# EM7SEGClk.net
KiCad netlist of a schematic drawn in EAGLE
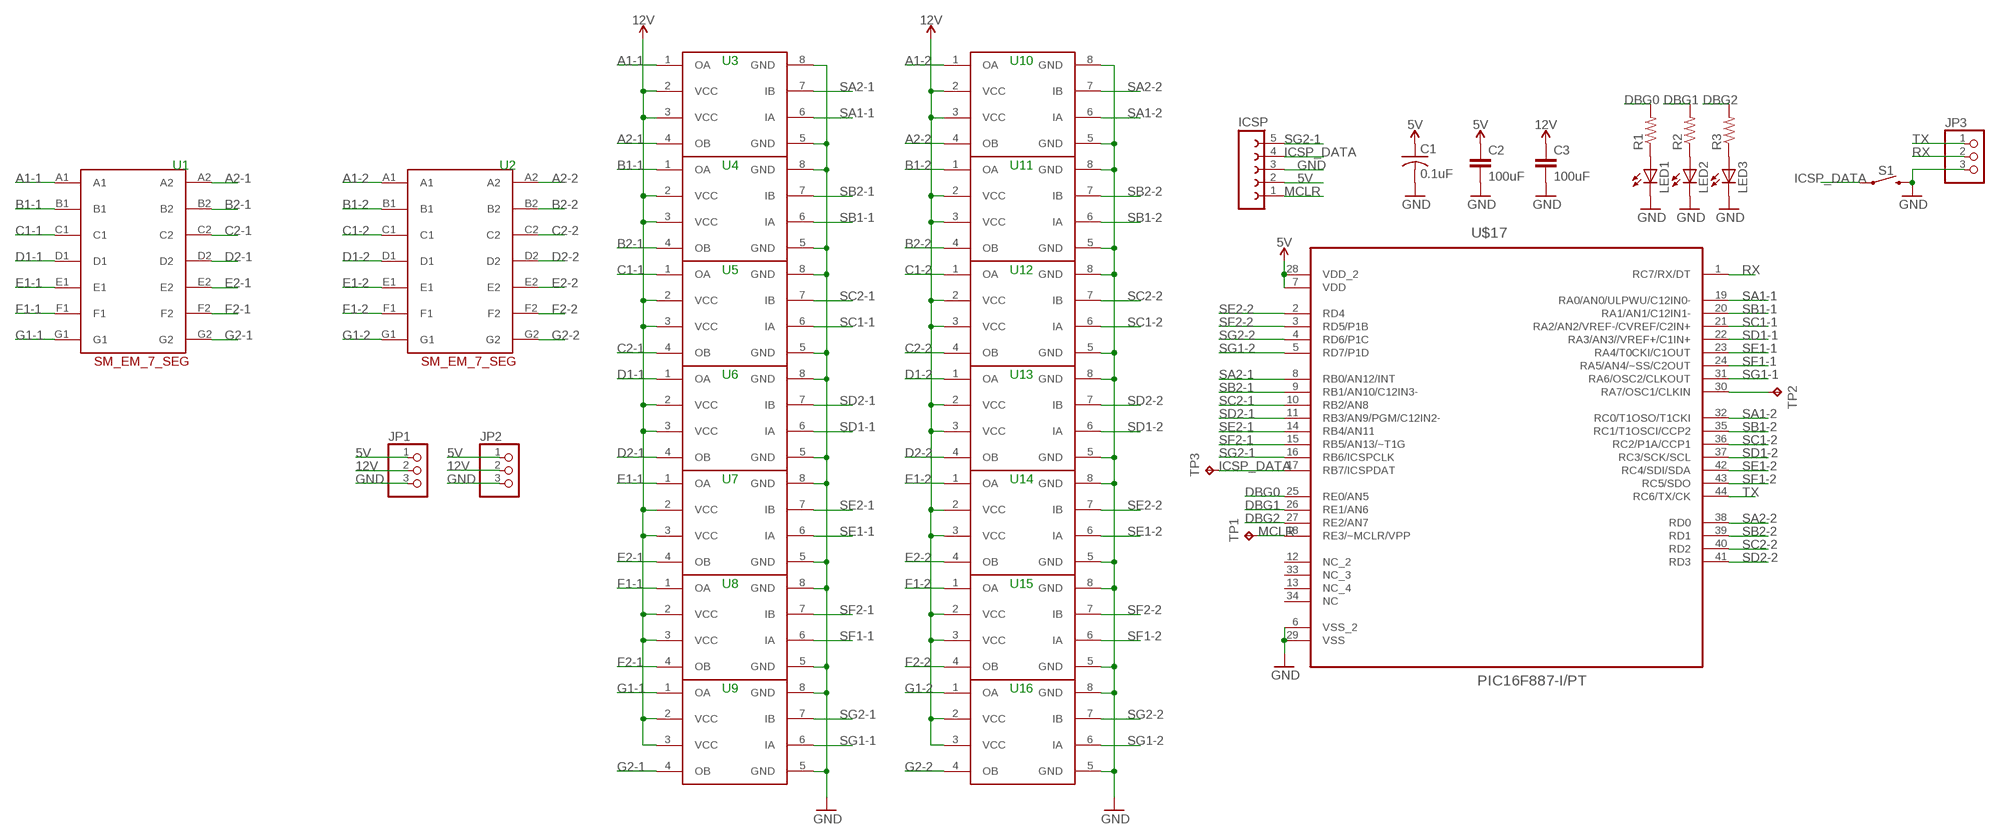
[diagram p0: schematic, sheet 1]

(export (version "E")
  (design (tool "Eeschema 10.0.6"))
  (components
    (comp (ref "C1")
      (value "0.1uF")
      (footprint "eagle-import:C0805")
      (libsource (lib "eagle-import") (part "C-USC0805"))
    )
    (comp (ref "C2")
      (value "100uF")
      (footprint "eagle-import:C5B2.5")
      (libsource (lib "eagle-import") (part "C5/2.5"))
    )
    (comp (ref "C3")
      (value "100uF")
      (footprint "eagle-import:C5B2.5")
      (libsource (lib "eagle-import") (part "C5/2.5"))
    )
    (comp (ref "ICSP")
      (value "FE05-1")
      (footprint "eagle-import:FE05-1")
      (libsource (lib "eagle-import") (part "FE05-1"))
    )
    (comp (ref "JP1")
      (value "PINHD-1X3CB")
      (footprint "eagle-import:1X03-CLEANBIG")
      (libsource (lib "eagle-import") (part "PINHD-1X3CB"))
    )
    (comp (ref "JP2")
      (value "PINHD-1X3CB")
      (footprint "eagle-import:1X03-CLEANBIG")
      (libsource (lib "eagle-import") (part "PINHD-1X3CB"))
    )
    (comp (ref "JP3")
      (value "PINHD-1X3CB")
      (footprint "eagle-import:1X03-CLEANBIG")
      (libsource (lib "eagle-import") (part "PINHD-1X3CB"))
    )
    (comp (ref "LED1")
      (value "LEDCHIPLED_0805")
      (footprint "eagle-import:CHIPLED_0805")
      (libsource (lib "eagle-import") (part "LEDCHIPLED_0805"))
    )
    (comp (ref "LED2")
      (value "LEDCHIPLED_0805")
      (footprint "eagle-import:CHIPLED_0805")
      (libsource (lib "eagle-import") (part "LEDCHIPLED_0805"))
    )
    (comp (ref "LED3")
      (value "LEDCHIPLED_0805")
      (footprint "eagle-import:CHIPLED_0805")
      (libsource (lib "eagle-import") (part "LEDCHIPLED_0805"))
    )
    (comp (ref "R1")
      (value "R-US_M0805")
      (footprint "eagle-import:M0805")
      (libsource (lib "eagle-import") (part "R-US_M0805"))
    )
    (comp (ref "R2")
      (value "R-US_M0805")
      (footprint "eagle-import:M0805")
      (libsource (lib "eagle-import") (part "R-US_M0805"))
    )
    (comp (ref "R3")
      (value "R-US_M0805")
      (footprint "eagle-import:M0805")
      (libsource (lib "eagle-import") (part "R-US_M0805"))
    )
    (comp (ref "S1")
      (value "MOMENTARY-SWITCH-SPST-PTH-6.0MM")
      (footprint "eagle-import:TACTILE_SWITCH_PTH_6.0MM")
      (libsource (lib "eagle-import") (part "MOMENTARY-SWITCH-SPST-PTH-6.0MM"))
    )
    (comp (ref "TP1")
      (value "TPTP16R")
      (footprint "eagle-import:TP16R")
      (libsource (lib "eagle-import") (part "TPTP16R"))
    )
    (comp (ref "TP2")
      (value "TPTP16R")
      (footprint "eagle-import:TP16R")
      (libsource (lib "eagle-import") (part "TPTP16R"))
    )
    (comp (ref "TP3")
      (value "TPTP16R")
      (footprint "eagle-import:TP16R")
      (libsource (lib "eagle-import") (part "TPTP16R"))
    )
    (comp (ref "U$1")
      (value "ELECTROMECHANICAL_7_SEG")
      (footprint "eagle-import:EM_7_SEG")
      (libsource (lib "eagle-import") (part "ELECTROMECHANICAL_7_SEG"))
    )
    (comp (ref "U$2")
      (value "ELECTROMECHANICAL_7_SEG")
      (footprint "eagle-import:EM_7_SEG")
      (libsource (lib "eagle-import") (part "ELECTROMECHANICAL_7_SEG"))
    )
    (comp (ref "U$3")
      (value "L9110SOP8")
      (footprint "eagle-import:SO8")
      (libsource (lib "eagle-import") (part "L9110SOP8"))
    )
    (comp (ref "U$4")
      (value "L9110SOP8")
      (footprint "eagle-import:SO8")
      (libsource (lib "eagle-import") (part "L9110SOP8"))
    )
    (comp (ref "U$5")
      (value "L9110SOP8")
      (footprint "eagle-import:SO8")
      (libsource (lib "eagle-import") (part "L9110SOP8"))
    )
    (comp (ref "U$6")
      (value "L9110SOP8")
      (footprint "eagle-import:SO8")
      (libsource (lib "eagle-import") (part "L9110SOP8"))
    )
    (comp (ref "U$7")
      (value "L9110SOP8")
      (footprint "eagle-import:SO8")
      (libsource (lib "eagle-import") (part "L9110SOP8"))
    )
    (comp (ref "U$8")
      (value "L9110SOP8")
      (footprint "eagle-import:SO8")
      (libsource (lib "eagle-import") (part "L9110SOP8"))
    )
    (comp (ref "U$9")
      (value "L9110SOP8")
      (footprint "eagle-import:SO8")
      (libsource (lib "eagle-import") (part "L9110SOP8"))
    )
    (comp (ref "U$10")
      (value "L9110SOP8")
      (footprint "eagle-import:SO8")
      (libsource (lib "eagle-import") (part "L9110SOP8"))
    )
    (comp (ref "U$14")
      (value "L9110SOP8")
      (footprint "eagle-import:SO8")
      (libsource (lib "eagle-import") (part "L9110SOP8"))
    )
    (comp (ref "U$15")
      (value "L9110SOP8")
      (footprint "eagle-import:SO8")
      (libsource (lib "eagle-import") (part "L9110SOP8"))
    )
    (comp (ref "U$16")
      (value "L9110SOP8")
      (footprint "eagle-import:SO8")
      (libsource (lib "eagle-import") (part "L9110SOP8"))
    )
    (comp (ref "U$17")
      (value "PIC16F887-I/PT")
      (footprint "eagle-import:QFP80P1200X1200X120-44N")
      (libsource (lib "eagle-import") (part "PIC16F887-I/PT"))
    )
    (comp (ref "U$140")
      (value "L9110SOP8")
      (footprint "eagle-import:SO8")
      (libsource (lib "eagle-import") (part "L9110SOP8"))
    )
    (comp (ref "U$150")
      (value "L9110SOP8")
      (footprint "eagle-import:SO8")
      (libsource (lib "eagle-import") (part "L9110SOP8"))
    )
    (comp (ref "U$160")
      (value "L9110SOP8")
      (footprint "eagle-import:SO8")
      (libsource (lib "eagle-import") (part "L9110SOP8"))
    )
  )
  (nets
    (net (code "1") (name "/A1-1") (class "Default")
      (node (ref "U$1") (pin "A1") (pinfunction "A1_A1") (pintype "bidirectional"))
      (node (ref "U$3") (pin "1") (pinfunction "OA_1") (pintype "bidirectional"))
    )
    (net (code "2") (name "/A1-2") (class "Default")
      (node (ref "U$10") (pin "1") (pinfunction "OA_1") (pintype "bidirectional"))
      (node (ref "U$2") (pin "A1") (pinfunction "A1_A1") (pintype "bidirectional"))
    )
    (net (code "3") (name "/A2-1") (class "Default")
      (node (ref "U$1") (pin "A2") (pinfunction "A2_A2") (pintype "bidirectional"))
      (node (ref "U$3") (pin "4") (pinfunction "OB_4") (pintype "bidirectional"))
    )
    (net (code "4") (name "/A2-2") (class "Default")
      (node (ref "U$10") (pin "4") (pinfunction "OB_4") (pintype "bidirectional"))
      (node (ref "U$2") (pin "A2") (pinfunction "A2_A2") (pintype "bidirectional"))
    )
    (net (code "5") (name "/B1-1") (class "Default")
      (node (ref "U$1") (pin "B1") (pinfunction "B1_B1") (pintype "bidirectional"))
      (node (ref "U$4") (pin "1") (pinfunction "OA_1") (pintype "bidirectional"))
    )
    (net (code "6") (name "/B1-2") (class "Default")
      (node (ref "U$140") (pin "1") (pinfunction "OA_1") (pintype "bidirectional"))
      (node (ref "U$2") (pin "B1") (pinfunction "B1_B1") (pintype "bidirectional"))
    )
    (net (code "7") (name "/B2-1") (class "Default")
      (node (ref "U$1") (pin "B2") (pinfunction "B2_B2") (pintype "bidirectional"))
      (node (ref "U$4") (pin "4") (pinfunction "OB_4") (pintype "bidirectional"))
    )
    (net (code "8") (name "/B2-2") (class "Default")
      (node (ref "U$140") (pin "4") (pinfunction "OB_4") (pintype "bidirectional"))
      (node (ref "U$2") (pin "B2") (pinfunction "B2_B2") (pintype "bidirectional"))
    )
    (net (code "9") (name "/C1-1") (class "Default")
      (node (ref "U$1") (pin "C1") (pinfunction "C1_C1") (pintype "bidirectional"))
      (node (ref "U$5") (pin "1") (pinfunction "OA_1") (pintype "bidirectional"))
    )
    (net (code "10") (name "/C1-2") (class "Default")
      (node (ref "U$150") (pin "1") (pinfunction "OA_1") (pintype "bidirectional"))
      (node (ref "U$2") (pin "C1") (pinfunction "C1_C1") (pintype "bidirectional"))
    )
    (net (code "11") (name "/C2-1") (class "Default")
      (node (ref "U$1") (pin "C2") (pinfunction "C2_C2") (pintype "bidirectional"))
      (node (ref "U$5") (pin "4") (pinfunction "OB_4") (pintype "bidirectional"))
    )
    (net (code "12") (name "/C2-2") (class "Default")
      (node (ref "U$150") (pin "4") (pinfunction "OB_4") (pintype "bidirectional"))
      (node (ref "U$2") (pin "C2") (pinfunction "C2_C2") (pintype "bidirectional"))
    )
    (net (code "13") (name "/D1-1") (class "Default")
      (node (ref "U$1") (pin "D1") (pinfunction "D1_D1") (pintype "bidirectional"))
      (node (ref "U$6") (pin "1") (pinfunction "OA_1") (pintype "bidirectional"))
    )
    (net (code "14") (name "/D1-2") (class "Default")
      (node (ref "U$160") (pin "1") (pinfunction "OA_1") (pintype "bidirectional"))
      (node (ref "U$2") (pin "D1") (pinfunction "D1_D1") (pintype "bidirectional"))
    )
    (net (code "15") (name "/D2-1") (class "Default")
      (node (ref "U$1") (pin "D2") (pinfunction "D2_D2") (pintype "bidirectional"))
      (node (ref "U$6") (pin "4") (pinfunction "OB_4") (pintype "bidirectional"))
    )
    (net (code "16") (name "/D2-2") (class "Default")
      (node (ref "U$160") (pin "4") (pinfunction "OB_4") (pintype "bidirectional"))
      (node (ref "U$2") (pin "D2") (pinfunction "D2_D2") (pintype "bidirectional"))
    )
    (net (code "17") (name "/DBG0") (class "Default")
      (node (ref "R1") (pin "2") (pinfunction "2_2") (pintype "passive"))
      (node (ref "U$17") (pin "25") (pinfunction "RE0/AN5_25") (pintype "bidirectional"))
    )
    (net (code "18") (name "/DBG1") (class "Default")
      (node (ref "R2") (pin "2") (pinfunction "2_2") (pintype "passive"))
      (node (ref "U$17") (pin "26") (pinfunction "RE1/AN6_26") (pintype "bidirectional"))
    )
    (net (code "19") (name "/DBG2") (class "Default")
      (node (ref "R3") (pin "2") (pinfunction "2_2") (pintype "passive"))
      (node (ref "U$17") (pin "27") (pinfunction "RE2/AN7_27") (pintype "bidirectional"))
    )
    (net (code "20") (name "/E1-1") (class "Default")
      (node (ref "U$1") (pin "E1") (pinfunction "E1_E1") (pintype "bidirectional"))
      (node (ref "U$7") (pin "1") (pinfunction "OA_1") (pintype "bidirectional"))
    )
    (net (code "21") (name "/E1-2") (class "Default")
      (node (ref "U$14") (pin "1") (pinfunction "OA_1") (pintype "bidirectional"))
      (node (ref "U$2") (pin "E1") (pinfunction "E1_E1") (pintype "bidirectional"))
    )
    (net (code "22") (name "/E2-1") (class "Default")
      (node (ref "U$1") (pin "E2") (pinfunction "E2_E2") (pintype "bidirectional"))
      (node (ref "U$7") (pin "4") (pinfunction "OB_4") (pintype "bidirectional"))
    )
    (net (code "23") (name "/E2-2") (class "Default")
      (node (ref "U$14") (pin "4") (pinfunction "OB_4") (pintype "bidirectional"))
      (node (ref "U$2") (pin "E2") (pinfunction "E2_E2") (pintype "bidirectional"))
    )
    (net (code "24") (name "/F1-1") (class "Default")
      (node (ref "U$1") (pin "F1") (pinfunction "F1_F1") (pintype "bidirectional"))
      (node (ref "U$8") (pin "1") (pinfunction "OA_1") (pintype "bidirectional"))
    )
    (net (code "25") (name "/F1-2") (class "Default")
      (node (ref "U$15") (pin "1") (pinfunction "OA_1") (pintype "bidirectional"))
      (node (ref "U$2") (pin "F1") (pinfunction "F1_F1") (pintype "bidirectional"))
    )
    (net (code "26") (name "/F2-1") (class "Default")
      (node (ref "U$1") (pin "F2") (pinfunction "F2_F2") (pintype "bidirectional"))
      (node (ref "U$8") (pin "4") (pinfunction "OB_4") (pintype "bidirectional"))
    )
    (net (code "27") (name "/F2-2") (class "Default")
      (node (ref "U$15") (pin "4") (pinfunction "OB_4") (pintype "bidirectional"))
      (node (ref "U$2") (pin "F2") (pinfunction "F2_F2") (pintype "bidirectional"))
    )
    (net (code "28") (name "/G1-1") (class "Default")
      (node (ref "U$1") (pin "G1") (pinfunction "G1_G1") (pintype "bidirectional"))
      (node (ref "U$9") (pin "1") (pinfunction "OA_1") (pintype "bidirectional"))
    )
    (net (code "29") (name "/G1-2") (class "Default")
      (node (ref "U$16") (pin "1") (pinfunction "OA_1") (pintype "bidirectional"))
      (node (ref "U$2") (pin "G1") (pinfunction "G1_G1") (pintype "bidirectional"))
    )
    (net (code "30") (name "/G2-1") (class "Default")
      (node (ref "U$1") (pin "G2") (pinfunction "G2_G2") (pintype "bidirectional"))
      (node (ref "U$9") (pin "4") (pinfunction "OB_4") (pintype "bidirectional"))
    )
    (net (code "31") (name "/G2-2") (class "Default")
      (node (ref "U$16") (pin "4") (pinfunction "OB_4") (pintype "bidirectional"))
      (node (ref "U$2") (pin "G2") (pinfunction "G2_G2") (pintype "bidirectional"))
    )
    (net (code "32") (name "/ICSP_DATA") (class "Default")
      (node (ref "ICSP") (pin "4") (pinfunction "4_4") (pintype "passive"))
      (node (ref "S1") (pin "1") (pinfunction "1_1") (pintype "passive"))
      (node (ref "TP3") (pin "TP") (pinfunction "TP_TP") (pintype "input"))
      (node (ref "U$17") (pin "17") (pinfunction "RB7/ICSPDAT_17") (pintype "bidirectional"))
    )
    (net (code "33") (name "/MCLR") (class "Default")
      (node (ref "ICSP") (pin "1") (pinfunction "1_1") (pintype "passive"))
      (node (ref "TP1") (pin "TP") (pinfunction "TP_TP") (pintype "input"))
      (node (ref "U$17") (pin "18") (pinfunction "RE3/~{MCLR/VPP}_18") (pintype "bidirectional"))
    )
    (net (code "34") (name "/RX") (class "Default")
      (node (ref "JP3") (pin "2") (pinfunction "2_2") (pintype "passive"))
      (node (ref "U$17") (pin "1") (pinfunction "RC7/RX/DT_1") (pintype "bidirectional"))
    )
    (net (code "35") (name "/SA1-1") (class "Default")
      (node (ref "U$17") (pin "19") (pinfunction "RA0/AN0/ULPWU/C12IN0-_19") (pintype "bidirectional"))
      (node (ref "U$3") (pin "6") (pinfunction "IA_6") (pintype "bidirectional"))
    )
    (net (code "36") (name "/SA1-2") (class "Default")
      (node (ref "U$10") (pin "6") (pinfunction "IA_6") (pintype "bidirectional"))
      (node (ref "U$17") (pin "32") (pinfunction "RC0/T1OSO/T1CKI_32") (pintype "bidirectional"))
    )
    (net (code "37") (name "/SA2-1") (class "Default")
      (node (ref "U$17") (pin "8") (pinfunction "RB0/AN12/INT_8") (pintype "bidirectional"))
      (node (ref "U$3") (pin "7") (pinfunction "IB_7") (pintype "bidirectional"))
    )
    (net (code "38") (name "/SA2-2") (class "Default")
      (node (ref "U$10") (pin "7") (pinfunction "IB_7") (pintype "bidirectional"))
      (node (ref "U$17") (pin "38") (pinfunction "RD0_38") (pintype "bidirectional"))
    )
    (net (code "39") (name "/SB1-1") (class "Default")
      (node (ref "U$17") (pin "20") (pinfunction "RA1/AN1/C12IN1-_20") (pintype "bidirectional"))
      (node (ref "U$4") (pin "6") (pinfunction "IA_6") (pintype "bidirectional"))
    )
    (net (code "40") (name "/SB1-2") (class "Default")
      (node (ref "U$140") (pin "6") (pinfunction "IA_6") (pintype "bidirectional"))
      (node (ref "U$17") (pin "35") (pinfunction "RC1/T1OSCI/CCP2_35") (pintype "bidirectional"))
    )
    (net (code "41") (name "/SB2-1") (class "Default")
      (node (ref "U$17") (pin "9") (pinfunction "RB1/AN10/C12IN3-_9") (pintype "bidirectional"))
      (node (ref "U$4") (pin "7") (pinfunction "IB_7") (pintype "bidirectional"))
    )
    (net (code "42") (name "/SB2-2") (class "Default")
      (node (ref "U$140") (pin "7") (pinfunction "IB_7") (pintype "bidirectional"))
      (node (ref "U$17") (pin "39") (pinfunction "RD1_39") (pintype "bidirectional"))
    )
    (net (code "43") (name "/SC1-1") (class "Default")
      (node (ref "U$17") (pin "21") (pinfunction "RA2/AN2/VREF-/CVREF/C2IN+_21") (pintype "bidirectional"))
      (node (ref "U$5") (pin "6") (pinfunction "IA_6") (pintype "bidirectional"))
    )
    (net (code "44") (name "/SC1-2") (class "Default")
      (node (ref "U$150") (pin "6") (pinfunction "IA_6") (pintype "bidirectional"))
      (node (ref "U$17") (pin "36") (pinfunction "RC2/P1A/CCP1_36") (pintype "bidirectional"))
    )
    (net (code "45") (name "/SC2-1") (class "Default")
      (node (ref "U$17") (pin "10") (pinfunction "RB2/AN8_10") (pintype "bidirectional"))
      (node (ref "U$5") (pin "7") (pinfunction "IB_7") (pintype "bidirectional"))
    )
    (net (code "46") (name "/SC2-2") (class "Default")
      (node (ref "U$150") (pin "7") (pinfunction "IB_7") (pintype "bidirectional"))
      (node (ref "U$17") (pin "40") (pinfunction "RD2_40") (pintype "bidirectional"))
    )
    (net (code "47") (name "/SD1-1") (class "Default")
      (node (ref "U$17") (pin "22") (pinfunction "RA3/AN3//VREF+/C1IN+_22") (pintype "bidirectional"))
      (node (ref "U$6") (pin "6") (pinfunction "IA_6") (pintype "bidirectional"))
    )
    (net (code "48") (name "/SD1-2") (class "Default")
      (node (ref "U$160") (pin "6") (pinfunction "IA_6") (pintype "bidirectional"))
      (node (ref "U$17") (pin "37") (pinfunction "RC3/SCK/SCL_37") (pintype "bidirectional"))
    )
    (net (code "49") (name "/SD2-1") (class "Default")
      (node (ref "U$17") (pin "11") (pinfunction "RB3/AN9/PGM/C12IN2-_11") (pintype "bidirectional"))
      (node (ref "U$6") (pin "7") (pinfunction "IB_7") (pintype "bidirectional"))
    )
    (net (code "50") (name "/SD2-2") (class "Default")
      (node (ref "U$160") (pin "7") (pinfunction "IB_7") (pintype "bidirectional"))
      (node (ref "U$17") (pin "41") (pinfunction "RD3_41") (pintype "bidirectional"))
    )
    (net (code "51") (name "/SE1-1") (class "Default")
      (node (ref "U$17") (pin "23") (pinfunction "RA4/T0CKI/C1OUT_23") (pintype "bidirectional"))
      (node (ref "U$7") (pin "6") (pinfunction "IA_6") (pintype "bidirectional"))
    )
    (net (code "52") (name "/SE1-2") (class "Default")
      (node (ref "U$14") (pin "6") (pinfunction "IA_6") (pintype "bidirectional"))
      (node (ref "U$17") (pin "42") (pinfunction "RC4/SDI/SDA_42") (pintype "bidirectional"))
    )
    (net (code "53") (name "/SE2-1") (class "Default")
      (node (ref "U$17") (pin "14") (pinfunction "RB4/AN11_14") (pintype "bidirectional"))
      (node (ref "U$7") (pin "7") (pinfunction "IB_7") (pintype "bidirectional"))
    )
    (net (code "54") (name "/SE2-2") (class "Default")
      (node (ref "U$14") (pin "7") (pinfunction "IB_7") (pintype "bidirectional"))
      (node (ref "U$17") (pin "2") (pinfunction "RD4_2") (pintype "bidirectional"))
    )
    (net (code "55") (name "/SF1-1") (class "Default")
      (node (ref "U$17") (pin "24") (pinfunction "RA5/AN4/~{SS/C2OUT}_24") (pintype "bidirectional"))
      (node (ref "U$8") (pin "6") (pinfunction "IA_6") (pintype "bidirectional"))
    )
    (net (code "56") (name "/SF1-2") (class "Default")
      (node (ref "U$15") (pin "6") (pinfunction "IA_6") (pintype "bidirectional"))
      (node (ref "U$17") (pin "43") (pinfunction "RC5/SDO_43") (pintype "bidirectional"))
    )
    (net (code "57") (name "/SF2-1") (class "Default")
      (node (ref "U$17") (pin "15") (pinfunction "RB5/AN13/~{T1G}_15") (pintype "bidirectional"))
      (node (ref "U$8") (pin "7") (pinfunction "IB_7") (pintype "bidirectional"))
    )
    (net (code "58") (name "/SF2-2") (class "Default")
      (node (ref "U$15") (pin "7") (pinfunction "IB_7") (pintype "bidirectional"))
      (node (ref "U$17") (pin "3") (pinfunction "RD5/P1B_3") (pintype "bidirectional"))
    )
    (net (code "59") (name "/SG1-1") (class "Default")
      (node (ref "U$17") (pin "31") (pinfunction "RA6/OSC2/CLKOUT_31") (pintype "bidirectional"))
      (node (ref "U$9") (pin "6") (pinfunction "IA_6") (pintype "bidirectional"))
    )
    (net (code "60") (name "/SG1-2") (class "Default")
      (node (ref "U$16") (pin "6") (pinfunction "IA_6") (pintype "bidirectional"))
      (node (ref "U$17") (pin "5") (pinfunction "RD7/P1D_5") (pintype "bidirectional"))
    )
    (net (code "61") (name "/SG2-1") (class "Default")
      (node (ref "ICSP") (pin "5") (pinfunction "5_5") (pintype "passive"))
      (node (ref "U$17") (pin "16") (pinfunction "RB6/ICSPCLK_16") (pintype "bidirectional"))
      (node (ref "U$9") (pin "7") (pinfunction "IB_7") (pintype "bidirectional"))
    )
    (net (code "62") (name "/SG2-2") (class "Default")
      (node (ref "U$16") (pin "7") (pinfunction "IB_7") (pintype "bidirectional"))
      (node (ref "U$17") (pin "4") (pinfunction "RD6/P1C_4") (pintype "bidirectional"))
    )
    (net (code "63") (name "/TX") (class "Default")
      (node (ref "JP3") (pin "1") (pinfunction "1_1") (pintype "passive"))
      (node (ref "U$17") (pin "44") (pinfunction "RC6/TX/CK_44") (pintype "bidirectional"))
    )
    (net (code "64") (name "5V") (class "Default")
      (node (ref "C1") (pin "1") (pinfunction "1_1") (pintype "passive"))
      (node (ref "C2") (pin "1") (pinfunction "1_1") (pintype "passive"))
      (node (ref "ICSP") (pin "2") (pinfunction "2_2") (pintype "passive"))
      (node (ref "JP1") (pin "1") (pinfunction "1_1") (pintype "passive"))
      (node (ref "JP2") (pin "1") (pinfunction "1_1") (pintype "passive"))
      (node (ref "U$17") (pin "28") (pinfunction "VDD_2_28") (pintype "power_in"))
      (node (ref "U$17") (pin "7") (pinfunction "VDD_7") (pintype "power_in"))
    )
    (net (code "65") (name "12V") (class "Default")
      (node (ref "C3") (pin "1") (pinfunction "1_1") (pintype "passive"))
      (node (ref "JP1") (pin "2") (pinfunction "2_2") (pintype "passive"))
      (node (ref "JP2") (pin "2") (pinfunction "2_2") (pintype "passive"))
      (node (ref "U$10") (pin "2") (pinfunction "VCC_2") (pintype "power_in"))
      (node (ref "U$10") (pin "3") (pinfunction "VCC_3") (pintype "power_in"))
      (node (ref "U$14") (pin "2") (pinfunction "VCC_2") (pintype "power_in"))
      (node (ref "U$14") (pin "3") (pinfunction "VCC_3") (pintype "power_in"))
      (node (ref "U$140") (pin "2") (pinfunction "VCC_2") (pintype "power_in"))
      (node (ref "U$140") (pin "3") (pinfunction "VCC_3") (pintype "power_in"))
      (node (ref "U$15") (pin "2") (pinfunction "VCC_2") (pintype "power_in"))
      (node (ref "U$15") (pin "3") (pinfunction "VCC_3") (pintype "power_in"))
      (node (ref "U$150") (pin "2") (pinfunction "VCC_2") (pintype "power_in"))
      (node (ref "U$150") (pin "3") (pinfunction "VCC_3") (pintype "power_in"))
      (node (ref "U$16") (pin "2") (pinfunction "VCC_2") (pintype "power_in"))
      (node (ref "U$16") (pin "3") (pinfunction "VCC_3") (pintype "power_in"))
      (node (ref "U$160") (pin "2") (pinfunction "VCC_2") (pintype "power_in"))
      (node (ref "U$160") (pin "3") (pinfunction "VCC_3") (pintype "power_in"))
      (node (ref "U$3") (pin "2") (pinfunction "VCC_2") (pintype "power_in"))
      (node (ref "U$3") (pin "3") (pinfunction "VCC_3") (pintype "power_in"))
      (node (ref "U$4") (pin "2") (pinfunction "VCC_2") (pintype "power_in"))
      (node (ref "U$4") (pin "3") (pinfunction "VCC_3") (pintype "power_in"))
      (node (ref "U$5") (pin "2") (pinfunction "VCC_2") (pintype "power_in"))
      (node (ref "U$5") (pin "3") (pinfunction "VCC_3") (pintype "power_in"))
      (node (ref "U$6") (pin "2") (pinfunction "VCC_2") (pintype "power_in"))
      (node (ref "U$6") (pin "3") (pinfunction "VCC_3") (pintype "power_in"))
      (node (ref "U$7") (pin "2") (pinfunction "VCC_2") (pintype "power_in"))
      (node (ref "U$7") (pin "3") (pinfunction "VCC_3") (pintype "power_in"))
      (node (ref "U$8") (pin "2") (pinfunction "VCC_2") (pintype "power_in"))
      (node (ref "U$8") (pin "3") (pinfunction "VCC_3") (pintype "power_in"))
      (node (ref "U$9") (pin "2") (pinfunction "VCC_2") (pintype "power_in"))
      (node (ref "U$9") (pin "3") (pinfunction "VCC_3") (pintype "power_in"))
    )
    (net (code "66") (name "GND") (class "Default")
      (node (ref "C1") (pin "2") (pinfunction "2_2") (pintype "passive"))
      (node (ref "C2") (pin "2") (pinfunction "2_2") (pintype "passive"))
      (node (ref "C3") (pin "2") (pinfunction "2_2") (pintype "passive"))
      (node (ref "ICSP") (pin "3") (pinfunction "3_3") (pintype "passive"))
      (node (ref "JP1") (pin "3") (pinfunction "3_3") (pintype "passive"))
      (node (ref "JP2") (pin "3") (pinfunction "3_3") (pintype "passive"))
      (node (ref "JP3") (pin "3") (pinfunction "3_3") (pintype "passive"))
      (node (ref "LED1") (pin "C") (pinfunction "C_C") (pintype "passive"))
      (node (ref "LED2") (pin "C") (pinfunction "C_C") (pintype "passive"))
      (node (ref "LED3") (pin "C") (pinfunction "C_C") (pintype "passive"))
      (node (ref "S1") (pin "3") (pinfunction "2_3") (pintype "passive"))
      (node (ref "U$10") (pin "5") (pinfunction "GND_5") (pintype "power_in"))
      (node (ref "U$10") (pin "8") (pinfunction "GND_8") (pintype "power_in"))
      (node (ref "U$14") (pin "5") (pinfunction "GND_5") (pintype "power_in"))
      (node (ref "U$14") (pin "8") (pinfunction "GND_8") (pintype "power_in"))
      (node (ref "U$140") (pin "5") (pinfunction "GND_5") (pintype "power_in"))
      (node (ref "U$140") (pin "8") (pinfunction "GND_8") (pintype "power_in"))
      (node (ref "U$15") (pin "5") (pinfunction "GND_5") (pintype "power_in"))
      (node (ref "U$15") (pin "8") (pinfunction "GND_8") (pintype "power_in"))
      (node (ref "U$150") (pin "5") (pinfunction "GND_5") (pintype "power_in"))
      (node (ref "U$150") (pin "8") (pinfunction "GND_8") (pintype "power_in"))
      (node (ref "U$16") (pin "5") (pinfunction "GND_5") (pintype "power_in"))
      (node (ref "U$16") (pin "8") (pinfunction "GND_8") (pintype "power_in"))
      (node (ref "U$160") (pin "5") (pinfunction "GND_5") (pintype "power_in"))
      (node (ref "U$160") (pin "8") (pinfunction "GND_8") (pintype "power_in"))
      (node (ref "U$17") (pin "29") (pinfunction "VSS_29") (pintype "passive"))
      (node (ref "U$17") (pin "6") (pinfunction "VSS_2_6") (pintype "passive"))
      (node (ref "U$3") (pin "5") (pinfunction "GND_5") (pintype "power_in"))
      (node (ref "U$3") (pin "8") (pinfunction "GND_8") (pintype "power_in"))
      (node (ref "U$4") (pin "5") (pinfunction "GND_5") (pintype "power_in"))
      (node (ref "U$4") (pin "8") (pinfunction "GND_8") (pintype "power_in"))
      (node (ref "U$5") (pin "5") (pinfunction "GND_5") (pintype "power_in"))
      (node (ref "U$5") (pin "8") (pinfunction "GND_8") (pintype "power_in"))
      (node (ref "U$6") (pin "5") (pinfunction "GND_5") (pintype "power_in"))
      (node (ref "U$6") (pin "8") (pinfunction "GND_8") (pintype "power_in"))
      (node (ref "U$7") (pin "5") (pinfunction "GND_5") (pintype "power_in"))
      (node (ref "U$7") (pin "8") (pinfunction "GND_8") (pintype "power_in"))
      (node (ref "U$8") (pin "5") (pinfunction "GND_5") (pintype "power_in"))
      (node (ref "U$8") (pin "8") (pinfunction "GND_8") (pintype "power_in"))
      (node (ref "U$9") (pin "5") (pinfunction "GND_5") (pintype "power_in"))
      (node (ref "U$9") (pin "8") (pinfunction "GND_8") (pintype "power_in"))
    )
    (net (code "67") (name "Net-(LED1-PadA)") (class "Default")
      (node (ref "LED1") (pin "A") (pinfunction "A_A") (pintype "passive"))
      (node (ref "R1") (pin "1") (pinfunction "1_1") (pintype "passive"))
    )
    (net (code "68") (name "Net-(LED2-PadA)") (class "Default")
      (node (ref "LED2") (pin "A") (pinfunction "A_A") (pintype "passive"))
      (node (ref "R2") (pin "1") (pinfunction "1_1") (pintype "passive"))
    )
    (net (code "69") (name "Net-(LED3-PadA)") (class "Default")
      (node (ref "LED3") (pin "A") (pinfunction "A_A") (pintype "passive"))
      (node (ref "R3") (pin "1") (pinfunction "1_1") (pintype "passive"))
    )
    (net (code "70") (name "Net-(U$17-RA7{slash}OSC1{slash}CLKIN)") (class "Default")
      (node (ref "TP2") (pin "TP") (pinfunction "TP_TP") (pintype "input"))
      (node (ref "U$17") (pin "30") (pinfunction "RA7/OSC1/CLKIN_30") (pintype "bidirectional"))
    )
    (net (code "71") (name "unconnected-(U$17-NC-Pad34)") (class "Default")
      (node (ref "U$17") (pin "34") (pinfunction "NC_34") (pintype "no_connect"))
    )
    (net (code "72") (name "unconnected-(U$17-NC_2-Pad12)") (class "Default")
      (node (ref "U$17") (pin "12") (pinfunction "NC_2_12") (pintype "no_connect"))
    )
    (net (code "73") (name "unconnected-(U$17-NC_3-Pad33)") (class "Default")
      (node (ref "U$17") (pin "33") (pinfunction "NC_3_33") (pintype "no_connect"))
    )
    (net (code "74") (name "unconnected-(U$17-NC_4-Pad13)") (class "Default")
      (node (ref "U$17") (pin "13") (pinfunction "NC_4_13") (pintype "no_connect"))
    )
  )
)
